# Top.net
KiCad netlist of a schematic drawn in Altium Designer
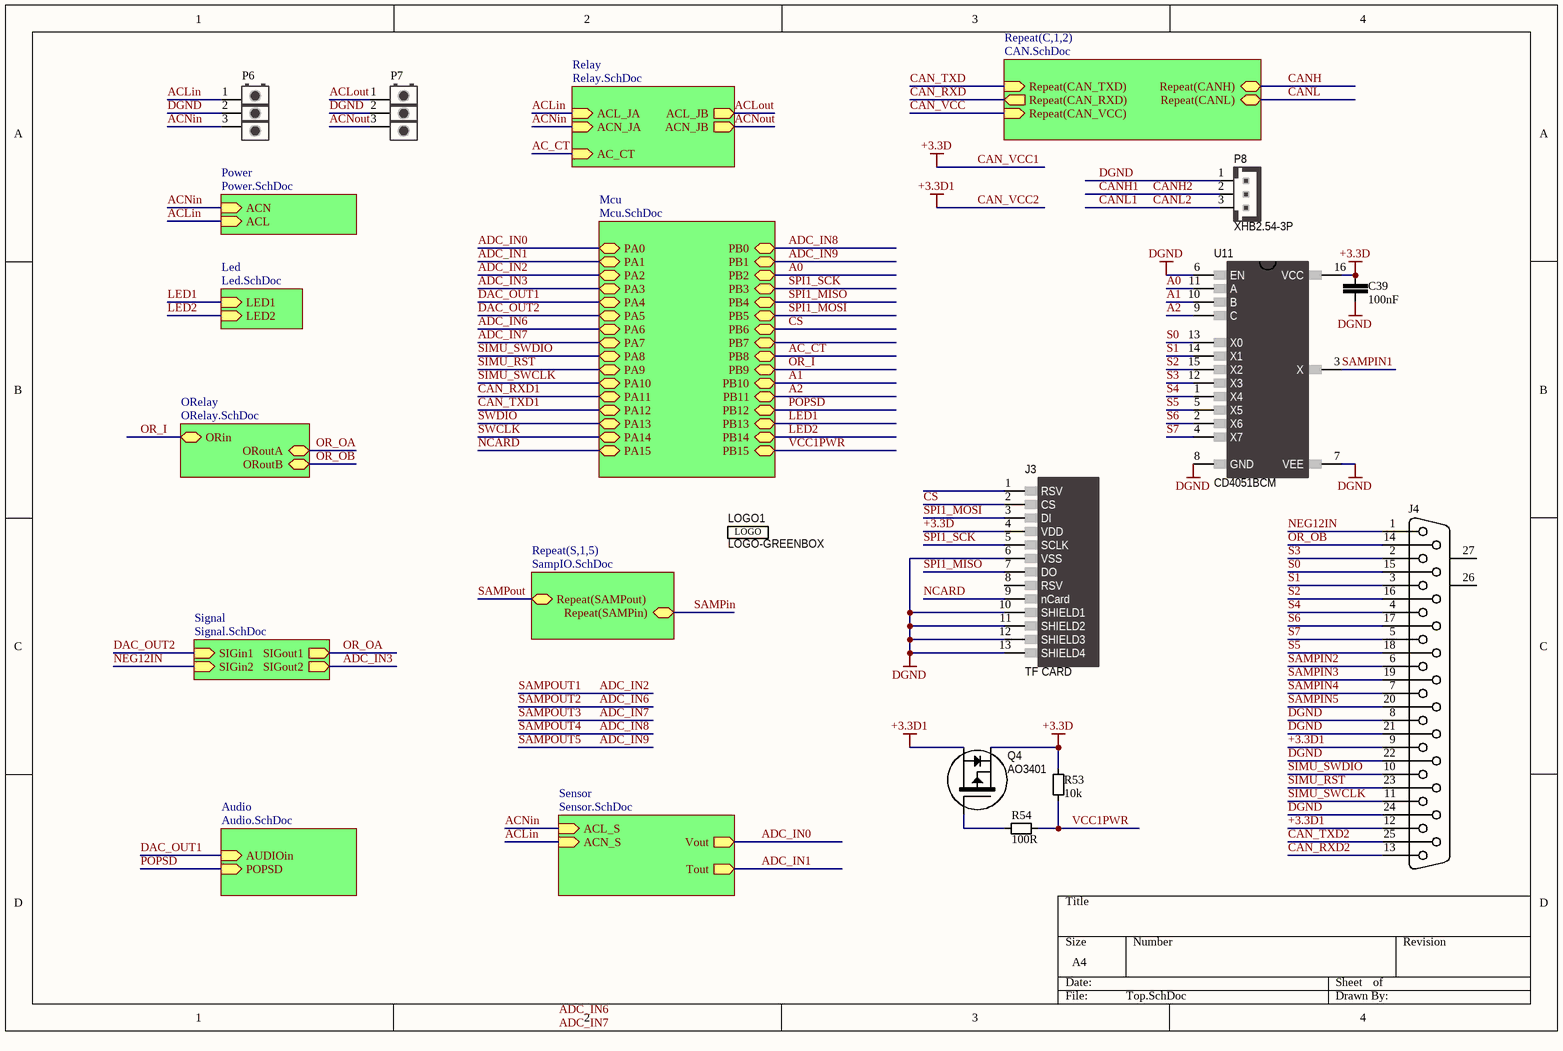
[diagram p0: Top.SchDoc]

(export (version "E")
  (design (tool "Eeschema 10.0.6"))
  (components
    (comp (ref "C39")
      (value "100nF")
      (footprint "GreenBox:0603-C")
      (description "MLCC 100nF 10% 50V X7R 0603")
      (fields (field (name "Comment") "Cap") (field (name "PUBLISHER") "GreenBox"))
      (libsource (lib "Capacitor") (part "C21C100NK1H0"))
    )
    (comp (ref "J3")
      (value "TF CARD")
      (footprint "GreenBox:TF-2")
      (description "TF CARD Pudsh-Push SPIMode")
      (fields (field (name "MANUFACTURER") "TEXAS INSTRUMENTS") (field (name "PUBLISHER") "GreenBox"))
      (libsource (lib "Miscellaneous") (part "M3DZTF2SPI00"))
    )
    (comp (ref "J4")
      (value "DB25")
      (footprint "GreenBox:DB25F")
      (description "Receptacle Assembly DB25 Vertical")
      (fields (field (name "PUBLISHER") "GreenBox"))
      (libsource (lib "Connectors") (part "PDDD25Z27700"))
    )
    (comp (ref "LOGO1")
      (value "LOGO-GREENBOX")
      (footprint "GreenBox:LOGO-GREENBOX")
      (description "Resettable Fuse SMD1206P050TF 1206 500mA")
      (fields (field (name "PUBLISHER") "GreenBox"))
      (libsource (lib "Miscellaneous") (part "LOGO1"))
    )
    (comp (ref "P6")
      (value "KF7.62-3P")
      (footprint "GreenBox:KF762-3")
      (description "Header KF7.62-3P 7.62mm")
      (fields (field (name "PUBLISHER") "GreenBox"))
      (libsource (lib "Connectors") (part "PKDK03Z76200"))
    )
    (comp (ref "P7")
      (value "KF7.62-3P")
      (footprint "GreenBox:KF762-3")
      (description "Header KF7.62-3P 7.62mm")
      (fields (field (name "PUBLISHER") "GreenBox"))
      (libsource (lib "Connectors") (part "PKDK03Z76200"))
    )
    (comp (ref "P8")
      (value "XHB2.54-3P")
      (footprint "GreenBox:XH-3")
      (description "Header XHB2.54-3P 2.54mm")
      (fields (field (name "PUBLISHER") "GreenBox"))
      (libsource (lib "Connectors") (part "P6DX03Z25400"))
    )
    (comp (ref "Q4")
      (value "AO3401")
      (footprint "GreenBox:SOT-23_N")
      (description "P-Channel MOSFET AO3401 -30V -4.2A")
      (fields (field (name "MANUFACTURER") "ALPHA&OMEGA") (field (name "PUBLISHER") "GreenBox"))
      (libsource (lib "MOSFET") (part "QP42AO34010A"))
    )
    (comp (ref "R53")
      (value "10k")
      (footprint "GreenBox:0603-R")
      (description "SMD Resistor 10k 1% 1/10W 0603 100PPM")
      (fields (field (name "Comment") "Res") (field (name "PUBLISHER") "GreenBox"))
      (libsource (lib "Resistor") (part "R11C010KFBF0"))
    )
    (comp (ref "R54")
      (value "100R")
      (footprint "GreenBox:0603-R")
      (description "SMD Resistor 100R 1% 1/10W 0603 100PPM")
      (fields (field (name "Comment") "Res") (field (name "PUBLISHER") "GreenBox"))
      (libsource (lib "Resistor") (part "R11C100RFBF0"))
    )
    (comp (ref "U11")
      (value "CD4051BCM")
      (footprint "GreenBox:SO-16_N")
      (description "SGL ENDED MULTIPLEXER CD4051BCM 8-CHANNEL")
      (fields (field (name "PUBLISHER") "GreenBox"))
      (libsource (lib "Semiconductor") (part "UCS3CD4051B0"))
    )
  )
  (nets
    (net (code "1") (name "+3.3D") (class "Default")
      (node (ref "C39") (pin "1") (pinfunction "1_1") (pintype "passive"))
      (node (ref "J3") (pin "4") (pinfunction "VDD_4") (pintype "passive"))
      (node (ref "Q4") (pin "2") (pinfunction "S_2") (pintype "passive"))
      (node (ref "R53") (pin "1") (pinfunction "1_1") (pintype "passive"))
      (node (ref "U11") (pin "16") (pinfunction "VCC_16") (pintype "passive"))
    )
    (net (code "2") (name "+3.3D1") (class "Default")
      (node (ref "J4") (pin "12") (pinfunction "12_12") (pintype "passive"))
      (node (ref "J4") (pin "9") (pinfunction "9_9") (pintype "passive"))
      (node (ref "Q4") (pin "3") (pinfunction "D_3") (pintype "passive"))
    )
    (net (code "3") (name "/A0") (class "Default")
      (node (ref "U11") (pin "11") (pinfunction "A_11") (pintype "passive"))
    )
    (net (code "4") (name "/A1") (class "Default")
      (node (ref "U11") (pin "10") (pinfunction "B_10") (pintype "passive"))
    )
    (net (code "5") (name "/A2") (class "Default")
      (node (ref "U11") (pin "9") (pinfunction "C_9") (pintype "passive"))
    )
    (net (code "6") (name "/ACLin") (class "Default")
      (node (ref "P6") (pin "1") (pinfunction "1_1") (pintype "passive"))
    )
    (net (code "7") (name "/ACLout") (class "Default")
      (node (ref "P7") (pin "1") (pinfunction "1_1") (pintype "passive"))
    )
    (net (code "8") (name "/ACNin") (class "Default")
      (node (ref "P6") (pin "3") (pinfunction "3_3") (pintype "passive"))
    )
    (net (code "9") (name "/ACNout") (class "Default")
      (node (ref "P7") (pin "3") (pinfunction "3_3") (pintype "passive"))
    )
    (net (code "20") (name "/CANH1") (class "Default")
      (node (ref "P8") (pin "2") (pinfunction "2_2") (pintype "passive"))
    )
    (net (code "22") (name "/CANL1") (class "Default")
      (node (ref "P8") (pin "3") (pinfunction "3_3") (pintype "passive"))
    )
    (net (code "25") (name "/CAN_RXD2") (class "Default")
      (node (ref "J4") (pin "13") (pinfunction "13_13") (pintype "passive"))
    )
    (net (code "28") (name "/CAN_TXD2") (class "Default")
      (node (ref "J4") (pin "25") (pinfunction "25_25") (pintype "passive"))
    )
    (net (code "30") (name "/CS") (class "Default")
      (node (ref "J3") (pin "2") (pinfunction "CS_2") (pintype "passive"))
    )
    (net (code "35") (name "/NCARD") (class "Default")
      (node (ref "J3") (pin "9") (pinfunction "nCard_9") (pintype "passive"))
    )
    (net (code "36") (name "/NEG12IN") (class "Default")
      (node (ref "J4") (pin "1") (pinfunction "1_1") (pintype "passive"))
    )
    (net (code "39") (name "/OR_OB") (class "Default")
      (node (ref "J4") (pin "14") (pinfunction "14_14") (pintype "passive"))
    )
    (net (code "42") (name "/S0") (class "Default")
      (node (ref "J4") (pin "15") (pinfunction "15_15") (pintype "passive"))
      (node (ref "U11") (pin "13") (pinfunction "X0_13") (pintype "passive"))
    )
    (net (code "43") (name "/S1") (class "Default")
      (node (ref "J4") (pin "3") (pinfunction "3_3") (pintype "passive"))
      (node (ref "U11") (pin "14") (pinfunction "X1_14") (pintype "passive"))
    )
    (net (code "44") (name "/S2") (class "Default")
      (node (ref "J4") (pin "16") (pinfunction "16_16") (pintype "passive"))
      (node (ref "U11") (pin "15") (pinfunction "X2_15") (pintype "passive"))
    )
    (net (code "45") (name "/S3") (class "Default")
      (node (ref "J4") (pin "2") (pinfunction "2_2") (pintype "passive"))
      (node (ref "U11") (pin "12") (pinfunction "X3_12") (pintype "passive"))
    )
    (net (code "46") (name "/S4") (class "Default")
      (node (ref "J4") (pin "4") (pinfunction "4_4") (pintype "passive"))
      (node (ref "U11") (pin "1") (pinfunction "X4_1") (pintype "passive"))
    )
    (net (code "47") (name "/S5") (class "Default")
      (node (ref "J4") (pin "18") (pinfunction "18_18") (pintype "passive"))
      (node (ref "U11") (pin "5") (pinfunction "X5_5") (pintype "passive"))
    )
    (net (code "48") (name "/S6") (class "Default")
      (node (ref "J4") (pin "17") (pinfunction "17_17") (pintype "passive"))
      (node (ref "U11") (pin "2") (pinfunction "X6_2") (pintype "passive"))
    )
    (net (code "49") (name "/S7") (class "Default")
      (node (ref "J4") (pin "5") (pinfunction "5_5") (pintype "passive"))
      (node (ref "U11") (pin "4") (pinfunction "X7_4") (pintype "passive"))
    )
    (net (code "50") (name "/SAMPIN1") (class "Default")
      (node (ref "U11") (pin "3") (pinfunction "X_3") (pintype "passive"))
    )
    (net (code "51") (name "/SAMPIN2") (class "Default")
      (node (ref "J4") (pin "6") (pinfunction "6_6") (pintype "passive"))
    )
    (net (code "52") (name "/SAMPIN3") (class "Default")
      (node (ref "J4") (pin "19") (pinfunction "19_19") (pintype "passive"))
    )
    (net (code "53") (name "/SAMPIN4") (class "Default")
      (node (ref "J4") (pin "7") (pinfunction "7_7") (pintype "passive"))
    )
    (net (code "54") (name "/SAMPIN5") (class "Default")
      (node (ref "J4") (pin "20") (pinfunction "20_20") (pintype "passive"))
    )
    (net (code "57") (name "/SIMU_RST") (class "Default")
      (node (ref "J4") (pin "23") (pinfunction "23_23") (pintype "passive"))
    )
    (net (code "58") (name "/SIMU_SWCLK") (class "Default")
      (node (ref "J4") (pin "11") (pinfunction "11_11") (pintype "passive"))
    )
    (net (code "59") (name "/SIMU_SWDIO") (class "Default")
      (node (ref "J4") (pin "10") (pinfunction "10_10") (pintype "passive"))
    )
    (net (code "60") (name "/SPI1_MISO") (class "Default")
      (node (ref "J3") (pin "7") (pinfunction "DO_7") (pintype "passive"))
    )
    (net (code "61") (name "/SPI1_MOSI") (class "Default")
      (node (ref "J3") (pin "3") (pinfunction "DI_3") (pintype "passive"))
    )
    (net (code "62") (name "/SPI1_SCK") (class "Default")
      (node (ref "J3") (pin "5") (pinfunction "SCLK_5") (pintype "passive"))
    )
    (net (code "65") (name "/VCC1PWR") (class "Default")
      (node (ref "R53") (pin "2") (pinfunction "2_2") (pintype "passive"))
      (node (ref "R54") (pin "2") (pinfunction "2_2") (pintype "passive"))
    )
    (net (code "66") (name "DGND") (class "Default")
      (node (ref "C39") (pin "2") (pinfunction "2_2") (pintype "passive"))
      (node (ref "J3") (pin "10") (pinfunction "SHIELD1_10") (pintype "passive"))
      (node (ref "J3") (pin "11") (pinfunction "SHIELD2_11") (pintype "passive"))
      (node (ref "J3") (pin "12") (pinfunction "SHIELD3_12") (pintype "passive"))
      (node (ref "J3") (pin "13") (pinfunction "SHIELD4_13") (pintype "passive"))
      (node (ref "J3") (pin "6") (pinfunction "VSS_6") (pintype "passive"))
      (node (ref "J4") (pin "21") (pinfunction "21_21") (pintype "passive"))
      (node (ref "J4") (pin "22") (pinfunction "22_22") (pintype "passive"))
      (node (ref "J4") (pin "24") (pinfunction "24_24") (pintype "passive"))
      (node (ref "J4") (pin "8") (pinfunction "8_8") (pintype "passive"))
      (node (ref "P6") (pin "2") (pinfunction "2_2") (pintype "passive"))
      (node (ref "P7") (pin "2") (pinfunction "2_2") (pintype "passive"))
      (node (ref "P8") (pin "1") (pinfunction "1_1") (pintype "passive"))
      (node (ref "U11") (pin "6") (pinfunction "EN_6") (pintype "passive"))
      (node (ref "U11") (pin "7") (pinfunction "VEE_7") (pintype "passive"))
      (node (ref "U11") (pin "8") (pinfunction "GND_8") (pintype "passive"))
    )
    (net (code "67") (name "Net-(Q4-G)") (class "Default")
      (node (ref "Q4") (pin "1") (pinfunction "G_1") (pintype "passive"))
      (node (ref "R54") (pin "1") (pinfunction "1_1") (pintype "passive"))
    )
    (net (code "68") (name "unconnected-(J3-RSV-Pad1)") (class "Default")
      (node (ref "J3") (pin "1") (pinfunction "RSV_1") (pintype "passive"))
    )
    (net (code "69") (name "unconnected-(J3-RSV-Pad8)") (class "Default")
      (node (ref "J3") (pin "8") (pinfunction "RSV_8") (pintype "passive"))
    )
    (net (code "70") (name "unconnected-(J4-MH1-Pad26)") (class "Default")
      (node (ref "J4") (pin "26") (pinfunction "MH1_26") (pintype "passive"))
    )
    (net (code "71") (name "unconnected-(J4-MH2-Pad27)") (class "Default")
      (node (ref "J4") (pin "27") (pinfunction "MH2_27") (pintype "passive"))
    )
  )
)
